# shinobi_BLE_analog.net
KiCad netlist of a schematic drawn in EAGLE
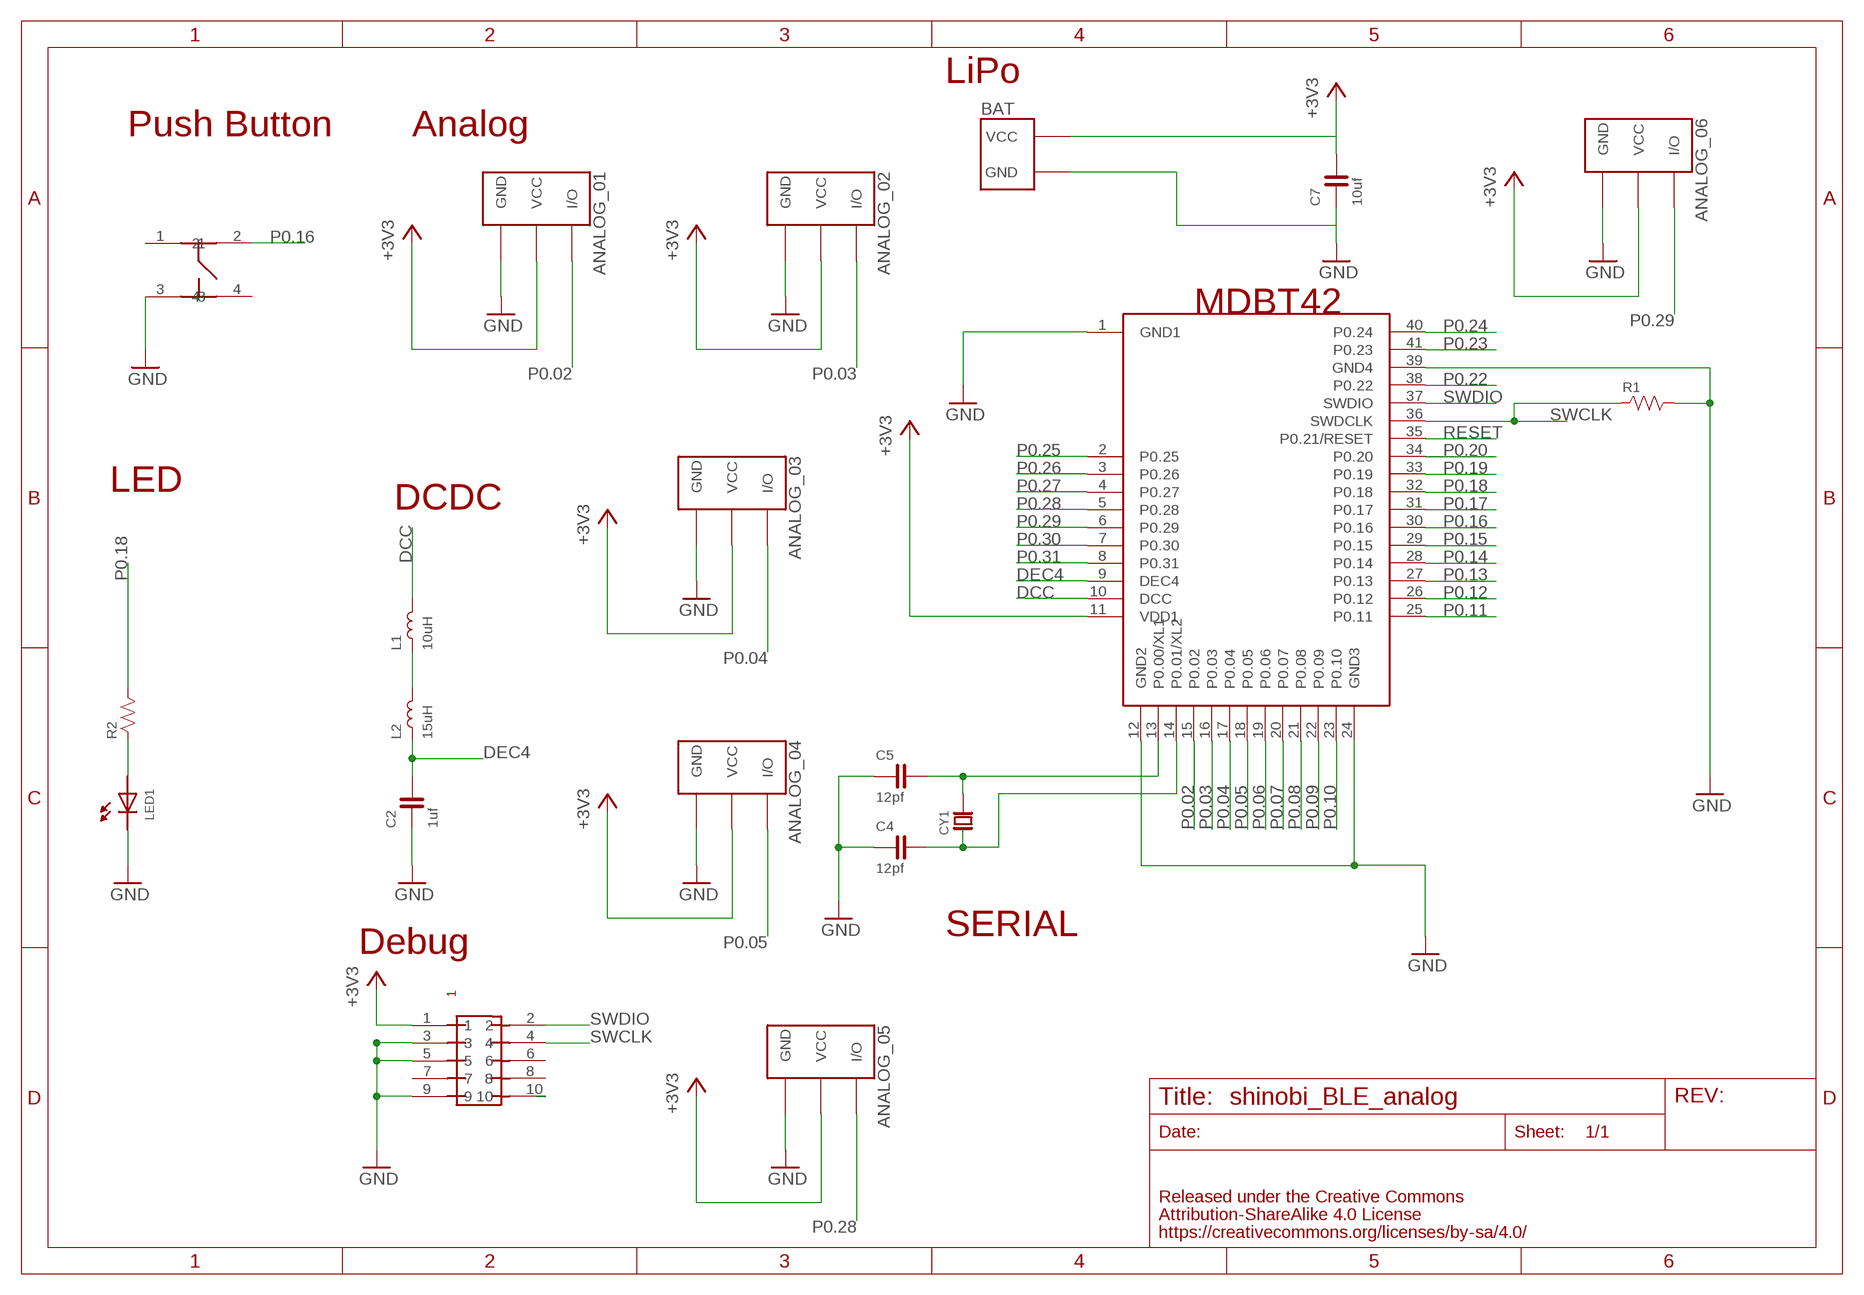
[diagram p0: schematic, sheet 1]

(export (version "E")
  (design (tool "Eeschema 10.0.6"))
  (components
    (comp (ref "ANALOG_01")
      (value "FABO_BRICK_3PIN-S03B-PASK-2_LONG")
      (footprint "eagle-import:FABO_BRICK_3PIN_S03B-PASK-2_LONG")
      (libsource (lib "eagle-import") (part "FABO_BRICK_3PIN-S03B-PASK-2_LONG"))
    )
    (comp (ref "ANALOG_02")
      (value "FABO_BRICK_3PIN-S03B-PASK-2_LONG")
      (footprint "eagle-import:FABO_BRICK_3PIN_S03B-PASK-2_LONG")
      (libsource (lib "eagle-import") (part "FABO_BRICK_3PIN-S03B-PASK-2_LONG"))
    )
    (comp (ref "ANALOG_03")
      (value "FABO_BRICK_3PIN-S03B-PASK-2_LONG")
      (footprint "eagle-import:FABO_BRICK_3PIN_S03B-PASK-2_LONG")
      (libsource (lib "eagle-import") (part "FABO_BRICK_3PIN-S03B-PASK-2_LONG"))
    )
    (comp (ref "ANALOG_04")
      (value "FABO_BRICK_3PIN-S03B-PASK-2_LONG")
      (footprint "eagle-import:FABO_BRICK_3PIN_S03B-PASK-2_LONG")
      (libsource (lib "eagle-import") (part "FABO_BRICK_3PIN-S03B-PASK-2_LONG"))
    )
    (comp (ref "ANALOG_05")
      (value "FABO_BRICK_3PIN-S03B-PASK-2_LONG")
      (footprint "eagle-import:FABO_BRICK_3PIN_S03B-PASK-2_LONG")
      (libsource (lib "eagle-import") (part "FABO_BRICK_3PIN-S03B-PASK-2_LONG"))
    )
    (comp (ref "ANALOG_06")
      (value "FABO_BRICK_3PIN-S03B-PASK-2_LONG")
      (footprint "eagle-import:FABO_BRICK_3PIN_S03B-PASK-2_LONG")
      (libsource (lib "eagle-import") (part "FABO_BRICK_3PIN-S03B-PASK-2_LONG"))
    )
    (comp (ref "BAT")
      (value "FABO_BRICK_2PIN_SIDE")
      (footprint "eagle-import:FABO_BRICK_2PIN_S02B−PASK-2_SILK")
      (libsource (lib "eagle-import") (part "FABO_BRICK_2PIN_SIDE"))
    )
    (comp (ref "C2")
      (value "1uf")
      (footprint "eagle-import:0603")
      (libsource (lib "eagle-import") (part "CAPACITOR-0603"))
    )
    (comp (ref "C4")
      (value "12pf")
      (footprint "eagle-import:0603")
      (libsource (lib "eagle-import") (part "CAPACITOR-0603"))
    )
    (comp (ref "C5")
      (value "12pf")
      (footprint "eagle-import:0603")
      (libsource (lib "eagle-import") (part "CAPACITOR-0603"))
    )
    (comp (ref "C7")
      (value "10uf")
      (footprint "eagle-import:0603")
      (libsource (lib "eagle-import") (part "CAPACITOR-0603"))
    )
    (comp (ref "CY1")
      (value "CRYSTAL-ABS07")
      (footprint "eagle-import:ABRACON-ABS07-32.768KHZ")
      (libsource (lib "eagle-import") (part "CRYSTAL-ABS07"))
    )
    (comp (ref "L1")
      (value "10uH")
      (footprint "eagle-import:0603")
      (libsource (lib "eagle-import") (part "INDUCTOR-0603"))
    )
    (comp (ref "L2")
      (value "15uH")
      (footprint "eagle-import:1812")
      (libsource (lib "eagle-import") (part "INDUCTOR-1812"))
    )
    (comp (ref "LED1")
      (value "LED-0603")
      (footprint "eagle-import:0603")
      (libsource (lib "eagle-import") (part "LED-0603"))
    )
    (comp (ref "R1")
      (value "RESISTOR-0603")
      (footprint "eagle-import:0603")
      (libsource (lib "eagle-import") (part "RESISTOR-0603"))
    )
    (comp (ref "R2")
      (value "RESISTOR-0603")
      (footprint "eagle-import:0603")
      (libsource (lib "eagle-import") (part "RESISTOR-0603"))
    )
    (comp (ref "U$2")
      (value "RAYTAC-MDBT42")
      (footprint "eagle-import:RAYTAC-MDBT42")
      (libsource (lib "eagle-import") (part "RAYTAC-MDBT42"))
    )
    (comp (ref "U$4")
      (value "PIN-HEADER-SMT(1.27MM)2X5")
      (footprint "eagle-import:PIN-HEADER-SMT(1.27MM)2X5")
      (libsource (lib "eagle-import") (part "PIN-HEADER-SMT(1.27MM)2X5"))
    )
    (comp (ref "U$5")
      (value "SWICTH-4P(KMR2)")
      (footprint "eagle-import:SWITCH-4P(KMR2)")
      (libsource (lib "eagle-import") (part "SWICTH-4P(KMR2)"))
    )
  )
  (nets
    (net (code "1") (name "+3V3") (class "Default")
      (node (ref "ANALOG_01") (pin "VCC") (pinfunction "VCC_VCC") (pintype "bidirectional"))
      (node (ref "ANALOG_02") (pin "VCC") (pinfunction "VCC_VCC") (pintype "bidirectional"))
      (node (ref "ANALOG_03") (pin "VCC") (pinfunction "VCC_VCC") (pintype "bidirectional"))
      (node (ref "ANALOG_04") (pin "VCC") (pinfunction "VCC_VCC") (pintype "bidirectional"))
      (node (ref "ANALOG_05") (pin "VCC") (pinfunction "VCC_VCC") (pintype "bidirectional"))
      (node (ref "ANALOG_06") (pin "VCC") (pinfunction "VCC_VCC") (pintype "bidirectional"))
      (node (ref "BAT") (pin "VCC") (pinfunction "VCC_VCC") (pintype "bidirectional"))
      (node (ref "C7") (pin "2") (pinfunction "2_2") (pintype "passive"))
      (node (ref "U$2") (pin "11") (pinfunction "VDD1_11") (pintype "bidirectional"))
      (node (ref "U$4") (pin "1") (pinfunction "1_1") (pintype "bidirectional"))
    )
    (net (code "2") (name "/DCC") (class "Default")
      (node (ref "L1") (pin "2") (pinfunction "2_2") (pintype "bidirectional"))
      (node (ref "U$2") (pin "10") (pinfunction "DCC_10") (pintype "bidirectional"))
    )
    (net (code "3") (name "/DEC4") (class "Default")
      (node (ref "C2") (pin "2") (pinfunction "2_2") (pintype "passive"))
      (node (ref "L2") (pin "P$1") (pinfunction "1_P$1") (pintype "bidirectional"))
      (node (ref "U$2") (pin "9") (pinfunction "DEC4_9") (pintype "bidirectional"))
    )
    (net (code "4") (name "/P0.02") (class "Default")
      (node (ref "ANALOG_01") (pin "I/O") (pinfunction "I/O_I/O") (pintype "bidirectional"))
      (node (ref "U$2") (pin "15") (pinfunction "P0.02_15") (pintype "bidirectional"))
    )
    (net (code "5") (name "/P0.03") (class "Default")
      (node (ref "ANALOG_02") (pin "I/O") (pinfunction "I/O_I/O") (pintype "bidirectional"))
      (node (ref "U$2") (pin "16") (pinfunction "P0.03_16") (pintype "bidirectional"))
    )
    (net (code "6") (name "/P0.04") (class "Default")
      (node (ref "ANALOG_03") (pin "I/O") (pinfunction "I/O_I/O") (pintype "bidirectional"))
      (node (ref "U$2") (pin "17") (pinfunction "P0.04_17") (pintype "bidirectional"))
    )
    (net (code "7") (name "/P0.05") (class "Default")
      (node (ref "ANALOG_04") (pin "I/O") (pinfunction "I/O_I/O") (pintype "bidirectional"))
      (node (ref "U$2") (pin "18") (pinfunction "P0.05_18") (pintype "bidirectional"))
    )
    (net (code "8") (name "/P0.06") (class "Default")
      (node (ref "U$2") (pin "19") (pinfunction "P0.06_19") (pintype "bidirectional"))
    )
    (net (code "9") (name "/P0.07") (class "Default")
      (node (ref "U$2") (pin "20") (pinfunction "P0.07_20") (pintype "bidirectional"))
    )
    (net (code "10") (name "/P0.08") (class "Default")
      (node (ref "U$2") (pin "21") (pinfunction "P0.08_21") (pintype "bidirectional"))
    )
    (net (code "11") (name "/P0.09") (class "Default")
      (node (ref "U$2") (pin "22") (pinfunction "P0.09_22") (pintype "bidirectional"))
    )
    (net (code "12") (name "/P0.10") (class "Default")
      (node (ref "U$2") (pin "23") (pinfunction "P0.10_23") (pintype "bidirectional"))
    )
    (net (code "13") (name "/P0.11") (class "Default")
      (node (ref "U$2") (pin "25") (pinfunction "P0.11_25") (pintype "bidirectional"))
    )
    (net (code "14") (name "/P0.12") (class "Default")
      (node (ref "U$2") (pin "26") (pinfunction "P0.12_26") (pintype "bidirectional"))
    )
    (net (code "15") (name "/P0.13") (class "Default")
      (node (ref "U$2") (pin "27") (pinfunction "P0.13_27") (pintype "bidirectional"))
    )
    (net (code "16") (name "/P0.14") (class "Default")
      (node (ref "U$2") (pin "28") (pinfunction "P0.14_28") (pintype "bidirectional"))
    )
    (net (code "17") (name "/P0.15") (class "Default")
      (node (ref "U$2") (pin "29") (pinfunction "P0.15_29") (pintype "bidirectional"))
    )
    (net (code "18") (name "/P0.16") (class "Default")
      (node (ref "U$2") (pin "30") (pinfunction "P0.16_30") (pintype "bidirectional"))
      (node (ref "U$5") (pin "2") (pinfunction "2_2") (pintype "bidirectional"))
    )
    (net (code "19") (name "/P0.17") (class "Default")
      (node (ref "U$2") (pin "31") (pinfunction "P0.17_31") (pintype "bidirectional"))
    )
    (net (code "20") (name "/P0.18") (class "Default")
      (node (ref "R2") (pin "2") (pinfunction "2_2") (pintype "bidirectional"))
      (node (ref "U$2") (pin "32") (pinfunction "P0.18_32") (pintype "bidirectional"))
    )
    (net (code "21") (name "/P0.19") (class "Default")
      (node (ref "U$2") (pin "33") (pinfunction "P0.19_33") (pintype "bidirectional"))
    )
    (net (code "22") (name "/P0.20") (class "Default")
      (node (ref "U$2") (pin "34") (pinfunction "P0.20_34") (pintype "bidirectional"))
    )
    (net (code "23") (name "/P0.22") (class "Default")
      (node (ref "U$2") (pin "38") (pinfunction "P0.22_38") (pintype "bidirectional"))
    )
    (net (code "24") (name "/P0.23") (class "Default")
      (node (ref "U$2") (pin "41") (pinfunction "P0.23_41") (pintype "bidirectional"))
    )
    (net (code "25") (name "/P0.24") (class "Default")
      (node (ref "U$2") (pin "40") (pinfunction "P0.24_40") (pintype "bidirectional"))
    )
    (net (code "26") (name "/P0.25") (class "Default")
      (node (ref "U$2") (pin "2") (pinfunction "P0.25_2") (pintype "bidirectional"))
    )
    (net (code "27") (name "/P0.26") (class "Default")
      (node (ref "U$2") (pin "3") (pinfunction "P0.26_3") (pintype "bidirectional"))
    )
    (net (code "28") (name "/P0.27") (class "Default")
      (node (ref "U$2") (pin "4") (pinfunction "P0.27_4") (pintype "bidirectional"))
    )
    (net (code "29") (name "/P0.28") (class "Default")
      (node (ref "ANALOG_05") (pin "I/O") (pinfunction "I/O_I/O") (pintype "bidirectional"))
      (node (ref "U$2") (pin "5") (pinfunction "P0.28_5") (pintype "bidirectional"))
    )
    (net (code "30") (name "/P0.29") (class "Default")
      (node (ref "ANALOG_06") (pin "I/O") (pinfunction "I/O_I/O") (pintype "bidirectional"))
      (node (ref "U$2") (pin "6") (pinfunction "P0.29_6") (pintype "bidirectional"))
    )
    (net (code "31") (name "/P0.30") (class "Default")
      (node (ref "U$2") (pin "7") (pinfunction "P0.30_7") (pintype "bidirectional"))
    )
    (net (code "32") (name "/P0.31") (class "Default")
      (node (ref "U$2") (pin "8") (pinfunction "P0.31_8") (pintype "bidirectional"))
    )
    (net (code "33") (name "/RESET") (class "Default")
      (node (ref "U$2") (pin "35") (pinfunction "P0.21/RESET_35") (pintype "bidirectional"))
    )
    (net (code "34") (name "/SWCLK") (class "Default")
      (node (ref "R1") (pin "1") (pinfunction "1_1") (pintype "bidirectional"))
      (node (ref "U$2") (pin "36") (pinfunction "SWDCLK_36") (pintype "bidirectional"))
      (node (ref "U$4") (pin "4") (pinfunction "4_4") (pintype "bidirectional"))
    )
    (net (code "35") (name "/SWDIO") (class "Default")
      (node (ref "U$2") (pin "37") (pinfunction "SWDIO_37") (pintype "bidirectional"))
      (node (ref "U$4") (pin "2") (pinfunction "2_2") (pintype "bidirectional"))
    )
    (net (code "36") (name "GND") (class "Default")
      (node (ref "ANALOG_01") (pin "GND") (pinfunction "GND_GND") (pintype "bidirectional"))
      (node (ref "ANALOG_02") (pin "GND") (pinfunction "GND_GND") (pintype "bidirectional"))
      (node (ref "ANALOG_03") (pin "GND") (pinfunction "GND_GND") (pintype "bidirectional"))
      (node (ref "ANALOG_04") (pin "GND") (pinfunction "GND_GND") (pintype "bidirectional"))
      (node (ref "ANALOG_05") (pin "GND") (pinfunction "GND_GND") (pintype "bidirectional"))
      (node (ref "ANALOG_06") (pin "GND") (pinfunction "GND_GND") (pintype "bidirectional"))
      (node (ref "BAT") (pin "GND") (pinfunction "GND_GND") (pintype "bidirectional"))
      (node (ref "C2") (pin "1") (pinfunction "1_1") (pintype "passive"))
      (node (ref "C4") (pin "1") (pinfunction "1_1") (pintype "passive"))
      (node (ref "C5") (pin "1") (pinfunction "1_1") (pintype "passive"))
      (node (ref "C7") (pin "1") (pinfunction "1_1") (pintype "passive"))
      (node (ref "LED1") (pin "CATHODE") (pinfunction "CATHODE_CATHODE") (pintype "passive"))
      (node (ref "R1") (pin "2") (pinfunction "2_2") (pintype "bidirectional"))
      (node (ref "U$2") (pin "1") (pinfunction "GND1_1") (pintype "bidirectional"))
      (node (ref "U$2") (pin "12") (pinfunction "GND2_12") (pintype "bidirectional"))
      (node (ref "U$2") (pin "24") (pinfunction "GND3_24") (pintype "bidirectional"))
      (node (ref "U$2") (pin "39") (pinfunction "GND4_39") (pintype "bidirectional"))
      (node (ref "U$4") (pin "3") (pinfunction "3_3") (pintype "bidirectional"))
      (node (ref "U$4") (pin "5") (pinfunction "5_5") (pintype "bidirectional"))
      (node (ref "U$4") (pin "9") (pinfunction "9_9") (pintype "bidirectional"))
      (node (ref "U$5") (pin "3") (pinfunction "3_3") (pintype "bidirectional"))
    )
    (net (code "37") (name "Net-(L2-2)") (class "Default")
      (node (ref "L1") (pin "1") (pinfunction "1_1") (pintype "bidirectional"))
      (node (ref "L2") (pin "P$2") (pinfunction "2_P$2") (pintype "bidirectional"))
    )
    (net (code "38") (name "Net-(LED1-PadANODE)") (class "Default")
      (node (ref "LED1") (pin "ANODE") (pinfunction "ANODE_ANODE") (pintype "passive"))
      (node (ref "R2") (pin "1") (pinfunction "1_1") (pintype "bidirectional"))
    )
    (net (code "39") (name "Net-(U$2-P0.00{slash}XL1)") (class "Default")
      (node (ref "C5") (pin "2") (pinfunction "2_2") (pintype "passive"))
      (node (ref "CY1") (pin "P$2") (pinfunction "P$2_P$2") (pintype "bidirectional"))
      (node (ref "U$2") (pin "13") (pinfunction "P0.00/XL1_13") (pintype "bidirectional"))
    )
    (net (code "40") (name "Net-(U$2-P0.01{slash}XL2)") (class "Default")
      (node (ref "C4") (pin "2") (pinfunction "2_2") (pintype "passive"))
      (node (ref "CY1") (pin "P$1") (pinfunction "P$1_P$1") (pintype "bidirectional"))
      (node (ref "U$2") (pin "14") (pinfunction "P0.01/XL2_14") (pintype "bidirectional"))
    )
    (net (code "41") (name "unconnected-(U$4-Pad6)") (class "Default")
      (node (ref "U$4") (pin "6") (pinfunction "6_6") (pintype "bidirectional"))
    )
    (net (code "42") (name "unconnected-(U$4-Pad7)") (class "Default")
      (node (ref "U$4") (pin "7") (pinfunction "7_7") (pintype "bidirectional"))
    )
    (net (code "43") (name "unconnected-(U$4-Pad8)") (class "Default")
      (node (ref "U$4") (pin "8") (pinfunction "8_8") (pintype "bidirectional"))
    )
    (net (code "44") (name "unconnected-(U$4-Pad10)") (class "Default")
      (node (ref "U$4") (pin "10") (pinfunction "10_10") (pintype "bidirectional"))
    )
    (net (code "45") (name "unconnected-(U$5-Pad1)") (class "Default")
      (node (ref "U$5") (pin "1") (pinfunction "1_1") (pintype "bidirectional"))
    )
    (net (code "46") (name "unconnected-(U$5-Pad4)") (class "Default")
      (node (ref "U$5") (pin "4") (pinfunction "4_4") (pintype "bidirectional"))
    )
  )
)
